# Discharge_circuit_1.net
KiCad netlist of a schematic drawn in Altium Designer
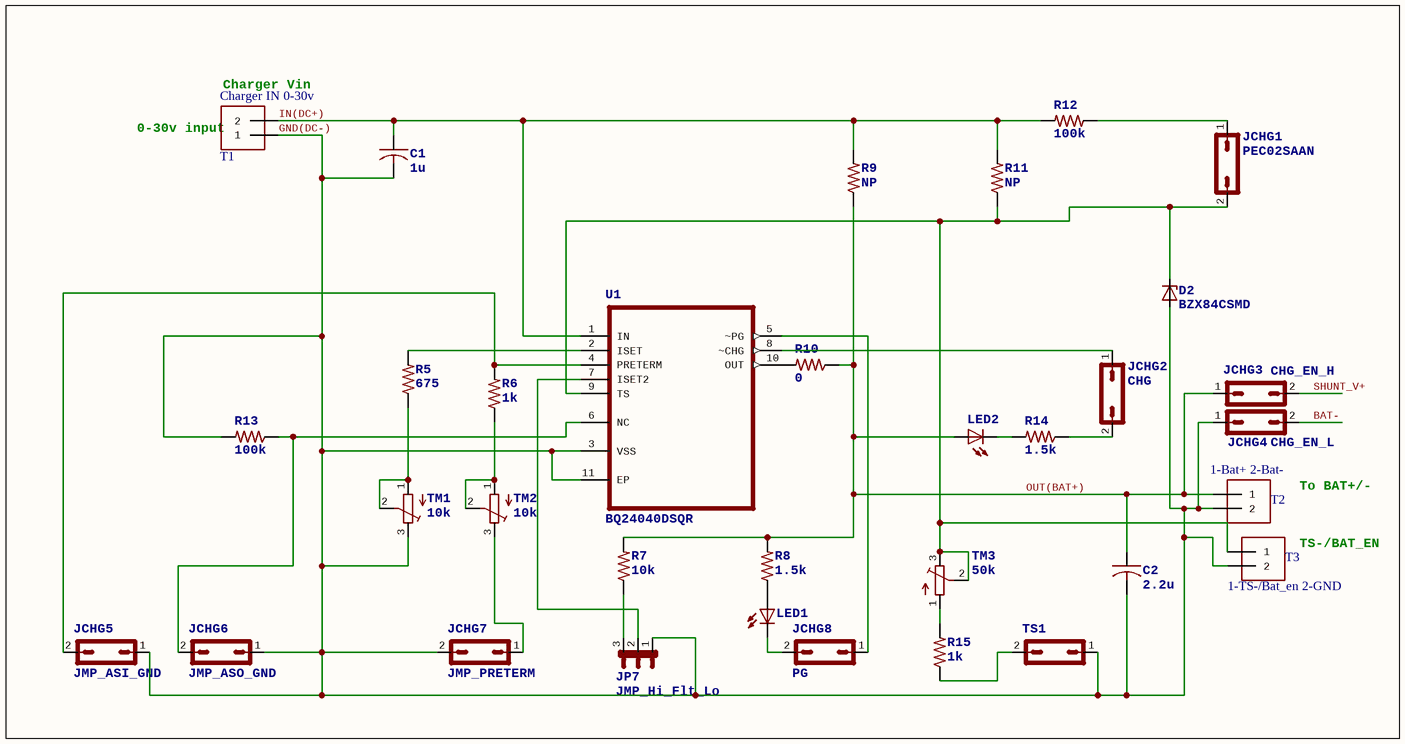
[diagram p0: Discharge_circuit_1.SchDoc]

(export (version "E")
  (design (tool "Eeschema 10.0.6"))
  (components
    (comp (ref "C1")
      (value "1u")
      (footprint "C1206")
      (description "CAPACITOR, American symbol")
      (libsource (lib "rcl") (part "C-USC1206"))
    )
    (comp (ref "C2")
      (value "2.2u")
      (footprint "C1206")
      (description "CAPACITOR, American symbol")
      (libsource (lib "rcl") (part "C-USC1206"))
    )
    (comp (ref "D2")
      (value "BZX84CSMD")
      (footprint "TO236")
      (description "Z DIODE")
      (libsource (lib "diode") (part "BZX84CSMD"))
    )
    (comp (ref "JCHG1")
      (value "PEC02SAAN")
      (footprint "JP1")
      (description "JUMPER")
      (libsource (lib "jumper") (part "JP1Q"))
    )
    (comp (ref "JCHG2")
      (value "CHG")
      (footprint "JP1")
      (description "JUMPER")
      (libsource (lib "jumper") (part "JP1Q"))
    )
    (comp (ref "JCHG3")
      (value "CHG_EN_H")
      (footprint "JP1")
      (description "JUMPER")
      (libsource (lib "jumper") (part "JP1Q"))
    )
    (comp (ref "JCHG4")
      (value "CHG_EN_L")
      (footprint "JP1")
      (description "JUMPER")
      (libsource (lib "jumper") (part "JP1Q"))
    )
    (comp (ref "JCHG5")
      (value "JMP_ASI_GND")
      (footprint "JP1")
      (description "JUMPER")
      (libsource (lib "jumper") (part "JP1Q"))
    )
    (comp (ref "JCHG6")
      (value "JMP_ASO_GND")
      (footprint "JP1")
      (description "JUMPER")
      (libsource (lib "jumper") (part "JP1Q"))
    )
    (comp (ref "JCHG7")
      (value "JMP_PRETERM")
      (footprint "JP1")
      (description "JUMPER")
      (libsource (lib "jumper") (part "JP1Q"))
    )
    (comp (ref "JCHG8")
      (value "PG")
      (footprint "JP1")
      (description "JUMPER")
      (libsource (lib "jumper") (part "JP1Q"))
    )
    (comp (ref "JP7")
      (value "JMP_Hi_Flt_Lo")
      (footprint "JP2")
      (description "JUMPER")
      (libsource (lib "jumper") (part "JP2E"))
    )
    (comp (ref "LED1")
      (value "~")
      (footprint "CHIPLED_1206")
      (libsource (lib "adafruit") (part "LEDCHIPLED_1206"))
    )
    (comp (ref "LED2")
      (value "~")
      (footprint "CHIPLED_1206")
      (libsource (lib "adafruit") (part "LEDCHIPLED_1206"))
    )
    (comp (ref "R5")
      (value "675")
      (footprint "R1206")
      (description "RESISTOR, American symbol")
      (libsource (lib "adafruit") (part "R-US_R1206"))
    )
    (comp (ref "R6")
      (value "1k")
      (footprint "R1206")
      (description "RESISTOR, American symbol")
      (libsource (lib "adafruit") (part "R-US_R1206"))
    )
    (comp (ref "R7")
      (value "10k")
      (footprint "R1206")
      (description "RESISTOR, American symbol")
      (libsource (lib "adafruit") (part "R-US_R1206"))
    )
    (comp (ref "R8")
      (value "1.5k")
      (footprint "R1206")
      (description "RESISTOR, American symbol")
      (libsource (lib "adafruit") (part "R-US_R1206"))
    )
    (comp (ref "R9")
      (value "NP")
      (footprint "R1206")
      (description "RESISTOR, American symbol")
      (libsource (lib "adafruit") (part "R-US_R1206"))
    )
    (comp (ref "R10")
      (value "0")
      (footprint "R0603")
      (description "RESISTOR, American symbol")
      (libsource (lib "adafruit") (part "R-US_R1206"))
    )
    (comp (ref "R11")
      (value "NP")
      (footprint "R1206")
      (description "RESISTOR, American symbol")
      (libsource (lib "adafruit") (part "R-US_R1206"))
    )
    (comp (ref "R12")
      (value "100k")
      (footprint "R1206")
      (description "RESISTOR, American symbol")
      (libsource (lib "adafruit") (part "R-US_R1206"))
    )
    (comp (ref "R13")
      (value "100k")
      (footprint "R1206")
      (description "RESISTOR, American symbol")
      (libsource (lib "adafruit") (part "R-US_R1206"))
    )
    (comp (ref "R14")
      (value "1.5k")
      (footprint "R1206")
      (description "RESISTOR, American symbol")
      (libsource (lib "adafruit") (part "R-US_R1206"))
    )
    (comp (ref "R15")
      (value "1k")
      (footprint "R1206")
      (description "RESISTOR, American symbol")
      (libsource (lib "adafruit") (part "R-US_R1206"))
    )
    (comp (ref "T1")
      (value "Charger IN 0-30v")
      (footprint "1X2-3.5MM")
      (description "3.5mm Terminal block    http://www.ladyada.net/library/pcb/eaglelibrary.html")
      (libsource (lib "adafruit") (part "1X2-3.5MM"))
    )
    (comp (ref "T2")
      (value "1-Bat+ 2-Bat-")
      (footprint "1X2-3.5MM")
      (description "3.5mm Terminal block    http://www.ladyada.net/library/pcb/eaglelibrary.html")
      (libsource (lib "adafruit") (part "1X2-3.5MM"))
    )
    (comp (ref "T3")
      (value "1-TS-/Bat_en 2-GND")
      (footprint "1X2-3.5MM")
      (description "3.5mm Terminal block    http://www.ladyada.net/library/pcb/eaglelibrary.html")
      (libsource (lib "adafruit") (part "1X2-3.5MM"))
    )
    (comp (ref "TM1")
      (value "10k")
      (footprint "TC33X")
      (description "SMT trimmer potentiometer part number TC33X    http://www.ladyada.net/library/eagle")
      (libsource (lib "adafruit") (part "TRIMPOTTC33X"))
    )
    (comp (ref "TM2")
      (value "10k")
      (footprint "TC33X")
      (description "SMT trimmer potentiometer part number TC33X    http://www.ladyada.net/library/eagle")
      (libsource (lib "adafruit") (part "TRIMPOTTC33X"))
    )
    (comp (ref "TM3")
      (value "50k")
      (footprint "TC33X")
      (description "SMT trimmer potentiometer part number TC33X    http://www.ladyada.net/library/eagle")
      (libsource (lib "adafruit") (part "TRIMPOTTC33X"))
    )
    (comp (ref "TS1")
      (value "~")
      (footprint "JP1")
      (description "JUMPER")
      (libsource (lib "jumper") (part "JP1Q"))
    )
    (comp (ref "U1")
      (value "BQ24040DSQR")
      (footprint "SON40P200X200X80-10N")
      (description "Single Cell Li-Ion Battery Charger")
      (libsource (lib "Texas Instruments_By_element14_Batch_1") (part "BQ24040DSQR"))
    )
  )
  (nets
    (net (code "1") (name "/BAT-") (class "Default")
      (node (ref "JCHG4") (pin "2") (pinfunction "2_2") (pintype "passive"))
    )
    (net (code "2") (name "/GND(DC-)") (class "Default")
      (node (ref "C1") (pin "2") (pinfunction "2_2") (pintype "passive"))
      (node (ref "C2") (pin "2") (pinfunction "2_2") (pintype "passive"))
      (node (ref "D2") (pin "A") (pinfunction "A_A") (pintype "passive"))
      (node (ref "JCHG4") (pin "1") (pinfunction "1_1") (pintype "passive"))
      (node (ref "JCHG5") (pin "1") (pinfunction "1_1") (pintype "passive"))
      (node (ref "JCHG6") (pin "1") (pinfunction "1_1") (pintype "passive"))
      (node (ref "JCHG7") (pin "2") (pinfunction "2_2") (pintype "passive"))
      (node (ref "JP7") (pin "1") (pinfunction "1_1") (pintype "passive"))
      (node (ref "R13") (pin "2") (pinfunction "2_2") (pintype "passive"))
      (node (ref "T1") (pin "1") (pinfunction "1_1") (pintype "passive"))
      (node (ref "T2") (pin "2") (pinfunction "2_2") (pintype "passive"))
      (node (ref "T3") (pin "2") (pinfunction "2_2") (pintype "passive"))
      (node (ref "TM1") (pin "3") (pinfunction "E_3") (pintype "passive"))
      (node (ref "TS1") (pin "1") (pinfunction "1_1") (pintype "passive"))
      (node (ref "U1") (pin "11") (pinfunction "EP_11") (pintype "passive"))
      (node (ref "U1") (pin "3") (pinfunction "VSS_3") (pintype "passive"))
    )
    (net (code "3") (name "/IN(DC+)") (class "Default")
      (node (ref "C1") (pin "1") (pinfunction "1_1") (pintype "passive"))
      (node (ref "R11") (pin "2") (pinfunction "2_2") (pintype "passive"))
      (node (ref "R12") (pin "2") (pinfunction "2_2") (pintype "passive"))
      (node (ref "R9") (pin "2") (pinfunction "2_2") (pintype "passive"))
      (node (ref "T1") (pin "2") (pinfunction "2_2") (pintype "passive"))
      (node (ref "U1") (pin "1") (pinfunction "IN_1") (pintype "passive"))
    )
    (net (code "4") (name "/OUT(BAT+)") (class "Default")
      (node (ref "C2") (pin "1") (pinfunction "1_1") (pintype "passive"))
      (node (ref "JCHG3") (pin "1") (pinfunction "1_1") (pintype "passive"))
      (node (ref "LED2") (pin "A") (pinfunction "A_A") (pintype "passive"))
      (node (ref "R10") (pin "1") (pinfunction "1_1") (pintype "passive"))
      (node (ref "R7") (pin "2") (pinfunction "2_2") (pintype "passive"))
      (node (ref "R8") (pin "2") (pinfunction "2_2") (pintype "passive"))
      (node (ref "R9") (pin "1") (pinfunction "1_1") (pintype "passive"))
      (node (ref "T2") (pin "1") (pinfunction "1_1") (pintype "passive"))
    )
    (net (code "5") (name "/SHUNT_V+") (class "Default")
      (node (ref "JCHG3") (pin "2") (pinfunction "2_2") (pintype "passive"))
    )
    (net (code "6") (name "Net-(JCHG1-Pad1)") (class "Default")
      (node (ref "JCHG1") (pin "1") (pinfunction "1_1") (pintype "passive"))
      (node (ref "R12") (pin "1") (pinfunction "1_1") (pintype "passive"))
    )
    (net (code "7") (name "Net-(JCHG2-Pad2)") (class "Default")
      (node (ref "JCHG2") (pin "2") (pinfunction "2_2") (pintype "passive"))
      (node (ref "R14") (pin "1") (pinfunction "1_1") (pintype "passive"))
    )
    (net (code "8") (name "Net-(JCHG8-Pad2)") (class "Default")
      (node (ref "JCHG8") (pin "2") (pinfunction "2_2") (pintype "passive"))
      (node (ref "LED1") (pin "C") (pinfunction "C_C") (pintype "passive"))
    )
    (net (code "9") (name "Net-(JP7-Pad3)") (class "Default")
      (node (ref "JP7") (pin "3") (pinfunction "3_3") (pintype "passive"))
      (node (ref "R7") (pin "1") (pinfunction "1_1") (pintype "passive"))
    )
    (net (code "10") (name "Net-(LED1-PadA)") (class "Default")
      (node (ref "LED1") (pin "A") (pinfunction "A_A") (pintype "passive"))
      (node (ref "R8") (pin "1") (pinfunction "1_1") (pintype "passive"))
    )
    (net (code "11") (name "Net-(LED2-PadC)") (class "Default")
      (node (ref "LED2") (pin "C") (pinfunction "C_C") (pintype "passive"))
      (node (ref "R14") (pin "2") (pinfunction "2_2") (pintype "passive"))
    )
    (net (code "12") (name "Net-(R15-Pad1)") (class "Default")
      (node (ref "R15") (pin "1") (pinfunction "1_1") (pintype "passive"))
      (node (ref "TS1") (pin "2") (pinfunction "2_2") (pintype "passive"))
    )
    (net (code "13") (name "Net-(TM1-A)") (class "Default")
      (node (ref "R5") (pin "1") (pinfunction "1_1") (pintype "passive"))
      (node (ref "TM1") (pin "1") (pinfunction "A_1") (pintype "passive"))
      (node (ref "TM1") (pin "2") (pinfunction "S_2") (pintype "passive"))
    )
    (net (code "14") (name "Net-(TM2-A)") (class "Default")
      (node (ref "R6") (pin "1") (pinfunction "1_1") (pintype "passive"))
      (node (ref "TM2") (pin "1") (pinfunction "A_1") (pintype "passive"))
      (node (ref "TM2") (pin "2") (pinfunction "S_2") (pintype "passive"))
    )
    (net (code "15") (name "Net-(TM2-E)") (class "Default")
      (node (ref "JCHG7") (pin "1") (pinfunction "1_1") (pintype "passive"))
      (node (ref "TM2") (pin "3") (pinfunction "E_3") (pintype "passive"))
    )
    (net (code "16") (name "Net-(TM3-A)") (class "Default")
      (node (ref "R15") (pin "2") (pinfunction "2_2") (pintype "passive"))
      (node (ref "TM3") (pin "1") (pinfunction "A_1") (pintype "passive"))
    )
    (net (code "17") (name "Net-(TM3-E)") (class "Default")
      (node (ref "D2") (pin "C") (pinfunction "C_C") (pintype "passive"))
      (node (ref "JCHG1") (pin "2") (pinfunction "2_2") (pintype "passive"))
      (node (ref "R11") (pin "1") (pinfunction "1_1") (pintype "passive"))
      (node (ref "T3") (pin "1") (pinfunction "1_1") (pintype "passive"))
      (node (ref "TM3") (pin "2") (pinfunction "S_2") (pintype "passive"))
      (node (ref "TM3") (pin "3") (pinfunction "E_3") (pintype "passive"))
      (node (ref "U1") (pin "9") (pinfunction "TS_9") (pintype "passive"))
    )
    (net (code "18") (name "Net-(U1-ISET)") (class "Default")
      (node (ref "R5") (pin "2") (pinfunction "2_2") (pintype "passive"))
      (node (ref "U1") (pin "2") (pinfunction "ISET_2") (pintype "passive"))
    )
    (net (code "19") (name "Net-(U1-ISET2)") (class "Default")
      (node (ref "JP7") (pin "2") (pinfunction "2_2") (pintype "passive"))
      (node (ref "U1") (pin "7") (pinfunction "ISET2_7") (pintype "passive"))
    )
    (net (code "20") (name "Net-(U1-NC)") (class "Default")
      (node (ref "JCHG6") (pin "2") (pinfunction "2_2") (pintype "passive"))
      (node (ref "R13") (pin "1") (pinfunction "1_1") (pintype "passive"))
      (node (ref "U1") (pin "6") (pinfunction "NC_6") (pintype "passive"))
    )
    (net (code "21") (name "Net-(U1-OUT)") (class "Default")
      (node (ref "R10") (pin "2") (pinfunction "2_2") (pintype "passive"))
      (node (ref "U1") (pin "10") (pinfunction "OUT_10") (pintype "output"))
    )
    (net (code "22") (name "Net-(U1-PRETERM)") (class "Default")
      (node (ref "JCHG5") (pin "2") (pinfunction "2_2") (pintype "passive"))
      (node (ref "R6") (pin "2") (pinfunction "2_2") (pintype "passive"))
      (node (ref "U1") (pin "4") (pinfunction "PRETERM_4") (pintype "passive"))
    )
    (net (code "23") (name "Net-(U1-~CHG)") (class "Default")
      (node (ref "JCHG2") (pin "1") (pinfunction "1_1") (pintype "passive"))
      (node (ref "U1") (pin "8") (pinfunction "~CHG_8") (pintype "output"))
    )
    (net (code "24") (name "Net-(U1-~PG)") (class "Default")
      (node (ref "JCHG8") (pin "1") (pinfunction "1_1") (pintype "passive"))
      (node (ref "U1") (pin "5") (pinfunction "~PG_5") (pintype "output"))
    )
  )
)
